# AST1031.net
KiCad netlist of a schematic drawn in EAGLE
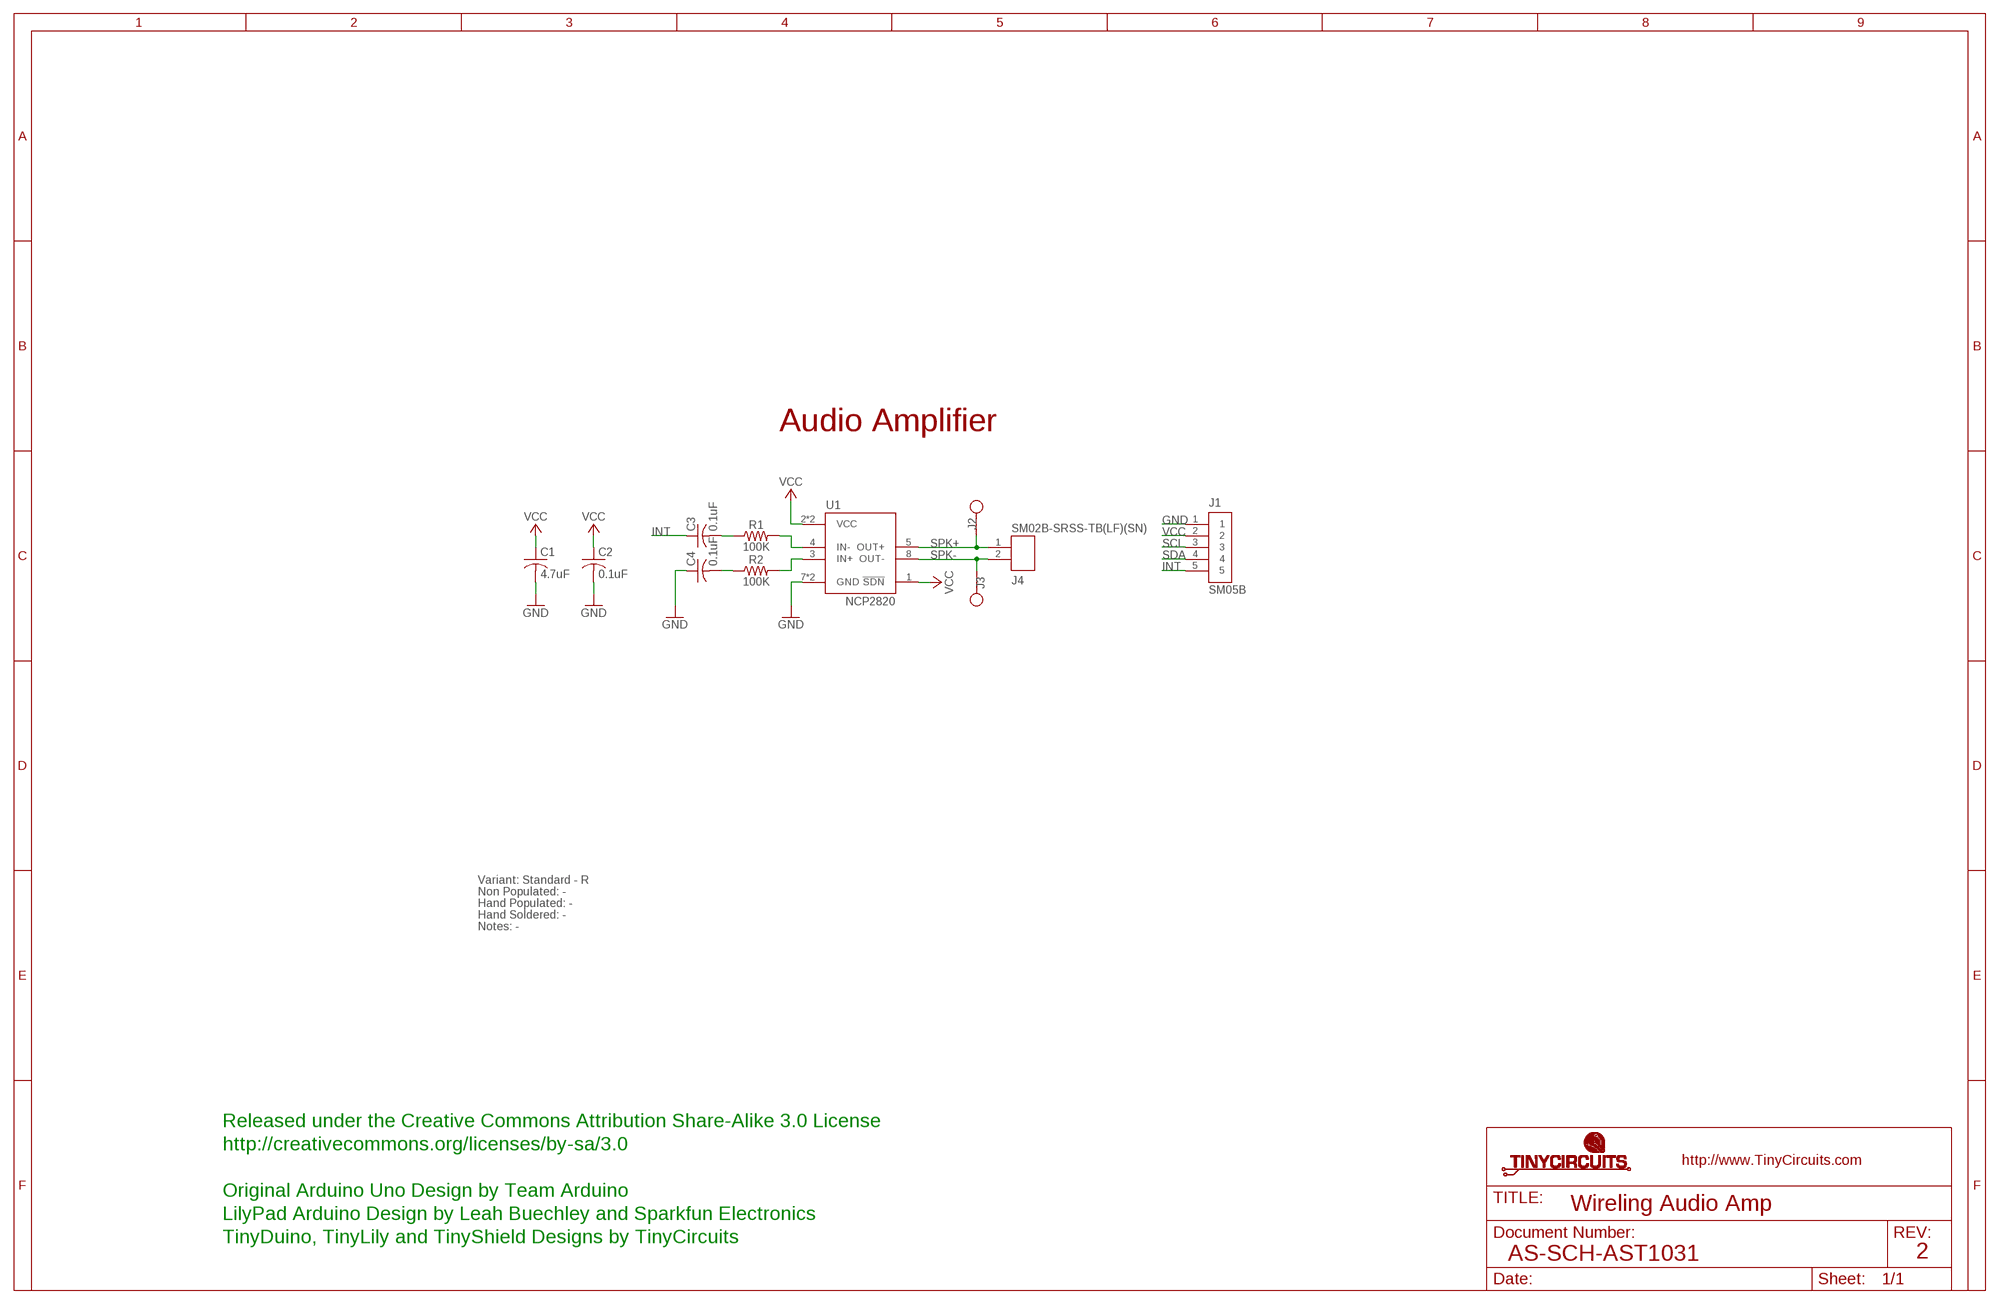
[diagram p0: schematic, sheet 1]

(export (version "E")
  (design (tool "Eeschema 10.0.6"))
  (components
    (comp (ref "C1")
      (value "4.7uF")
      (footprint "eagle-import:C0603")
      (fields (field (name "PARTNO") "AS-ITM-00088") (field (name "PARTNO_1") "AS-ITM-00088"))
      (libsource (lib "eagle-import") (part "AS-ITM-00088"))
    )
    (comp (ref "C2")
      (value "0.1uF")
      (footprint "eagle-import:C0402")
      (fields (field (name "PARTNO") "AS-ITM-00008"))
      (libsource (lib "eagle-import") (part "AS-ITM-00008"))
    )
    (comp (ref "C3")
      (value "0.1uF")
      (footprint "eagle-import:C0402")
      (fields (field (name "PARTNO") "AS-ITM-00008"))
      (libsource (lib "eagle-import") (part "AS-ITM-00008"))
    )
    (comp (ref "C4")
      (value "0.1uF")
      (footprint "eagle-import:C0402")
      (fields (field (name "PARTNO") "AS-ITM-00008"))
      (libsource (lib "eagle-import") (part "AS-ITM-00008"))
    )
    (comp (ref "J1")
      (value "SM05B")
      (footprint "eagle-import:JST_SH_5X1_EDGE")
      (fields (field (name "PARTNO") "AS-ITM-00340"))
      (libsource (lib "eagle-import") (part "AS-ITM-00340EDGE"))
    )
    (comp (ref "J2")
      (value "0.78MM_TH")
      (footprint "eagle-import:0.78MM_TH")
      (libsource (lib "eagle-import") (part "0.78MM_TH"))
    )
    (comp (ref "J3")
      (value "0.78MM_TH")
      (footprint "eagle-import:0.78MM_TH")
      (libsource (lib "eagle-import") (part "0.78MM_TH"))
    )
    (comp (ref "J4")
      (value "SM02B-SRSS-TB(LF)(SN)")
      (footprint "eagle-import:JST_SH_2X1")
      (fields (field (name "PARTNO") "AS-ITM-00231"))
      (libsource (lib "eagle-import") (part "AS-ITM-00231"))
    )
    (comp (ref "R1")
      (value "100K")
      (footprint "eagle-import:0402")
      (fields (field (name "PARTNO") "AS-ITM-00004"))
      (libsource (lib "eagle-import") (part "AS-ITM-00004"))
    )
    (comp (ref "R2")
      (value "100K")
      (footprint "eagle-import:0402")
      (fields (field (name "PARTNO") "AS-ITM-00004"))
      (libsource (lib "eagle-import") (part "AS-ITM-00004"))
    )
    (comp (ref "U1")
      (value "NCP2820")
      (footprint "eagle-import:WSON-8")
      (fields (field (name "PARTNO") "AS-ITM-00370"))
      (libsource (lib "eagle-import") (part "AS-ITM-00370"))
    )
  )
  (nets
    (net (code "1") (name "/INT") (class "Default")
      (node (ref "C3") (pin "1") (pinfunction "1_1") (pintype "passive"))
      (node (ref "J1") (pin "5") (pinfunction "5_5") (pintype "bidirectional"))
    )
    (net (code "2") (name "/SCL") (class "Default")
      (node (ref "J1") (pin "3") (pinfunction "3_3") (pintype "bidirectional"))
    )
    (net (code "3") (name "/SDA") (class "Default")
      (node (ref "J1") (pin "4") (pinfunction "4_4") (pintype "bidirectional"))
    )
    (net (code "4") (name "/SPK+") (class "Default")
      (node (ref "J2") (pin "P$1") (pinfunction "1_P$1") (pintype "bidirectional"))
      (node (ref "J4") (pin "1") (pinfunction "2_1") (pintype "bidirectional"))
      (node (ref "U1") (pin "5") (pinfunction "OUT+_5") (pintype "bidirectional"))
    )
    (net (code "5") (name "/SPK-") (class "Default")
      (node (ref "J3") (pin "P$1") (pinfunction "1_P$1") (pintype "bidirectional"))
      (node (ref "J4") (pin "2") (pinfunction "1_2") (pintype "bidirectional"))
      (node (ref "U1") (pin "8") (pinfunction "OUT-_8") (pintype "bidirectional"))
    )
    (net (code "6") (name "GND") (class "Default")
      (node (ref "C1") (pin "2") (pinfunction "2_2") (pintype "passive"))
      (node (ref "C2") (pin "2") (pinfunction "2_2") (pintype "passive"))
      (node (ref "C4") (pin "1") (pinfunction "1_1") (pintype "passive"))
      (node (ref "J1") (pin "1") (pinfunction "1_1") (pintype "bidirectional"))
      (node (ref "U1") (pin "7") (pinfunction "GND_7") (pintype "bidirectional"))
      (node (ref "U1") (pin "9") (pinfunction "GND_9") (pintype "bidirectional"))
    )
    (net (code "7") (name "Net-(C3-Pad2)") (class "Default")
      (node (ref "C3") (pin "2") (pinfunction "2_2") (pintype "passive"))
      (node (ref "R1") (pin "1") (pinfunction "1_1") (pintype "passive"))
    )
    (net (code "8") (name "Net-(C4-Pad2)") (class "Default")
      (node (ref "C4") (pin "2") (pinfunction "2_2") (pintype "passive"))
      (node (ref "R2") (pin "1") (pinfunction "1_1") (pintype "passive"))
    )
    (net (code "9") (name "Net-(U1-IN+)") (class "Default")
      (node (ref "R2") (pin "2") (pinfunction "2_2") (pintype "passive"))
      (node (ref "U1") (pin "3") (pinfunction "IN+_3") (pintype "bidirectional"))
    )
    (net (code "10") (name "Net-(U1-IN-)") (class "Default")
      (node (ref "R1") (pin "2") (pinfunction "2_2") (pintype "passive"))
      (node (ref "U1") (pin "4") (pinfunction "IN-_4") (pintype "bidirectional"))
    )
    (net (code "11") (name "VCC") (class "Default")
      (node (ref "C1") (pin "1") (pinfunction "1_1") (pintype "passive"))
      (node (ref "C2") (pin "1") (pinfunction "1_1") (pintype "passive"))
      (node (ref "J1") (pin "2") (pinfunction "2_2") (pintype "bidirectional"))
      (node (ref "U1") (pin "1") (pinfunction "~{SDN}_1") (pintype "bidirectional"))
      (node (ref "U1") (pin "2") (pinfunction "VCC_2") (pintype "bidirectional"))
      (node (ref "U1") (pin "6") (pinfunction "VCC_6") (pintype "bidirectional"))
    )
  )
)
